# W010X.net
KiCad netlist of a schematic drawn in EAGLE
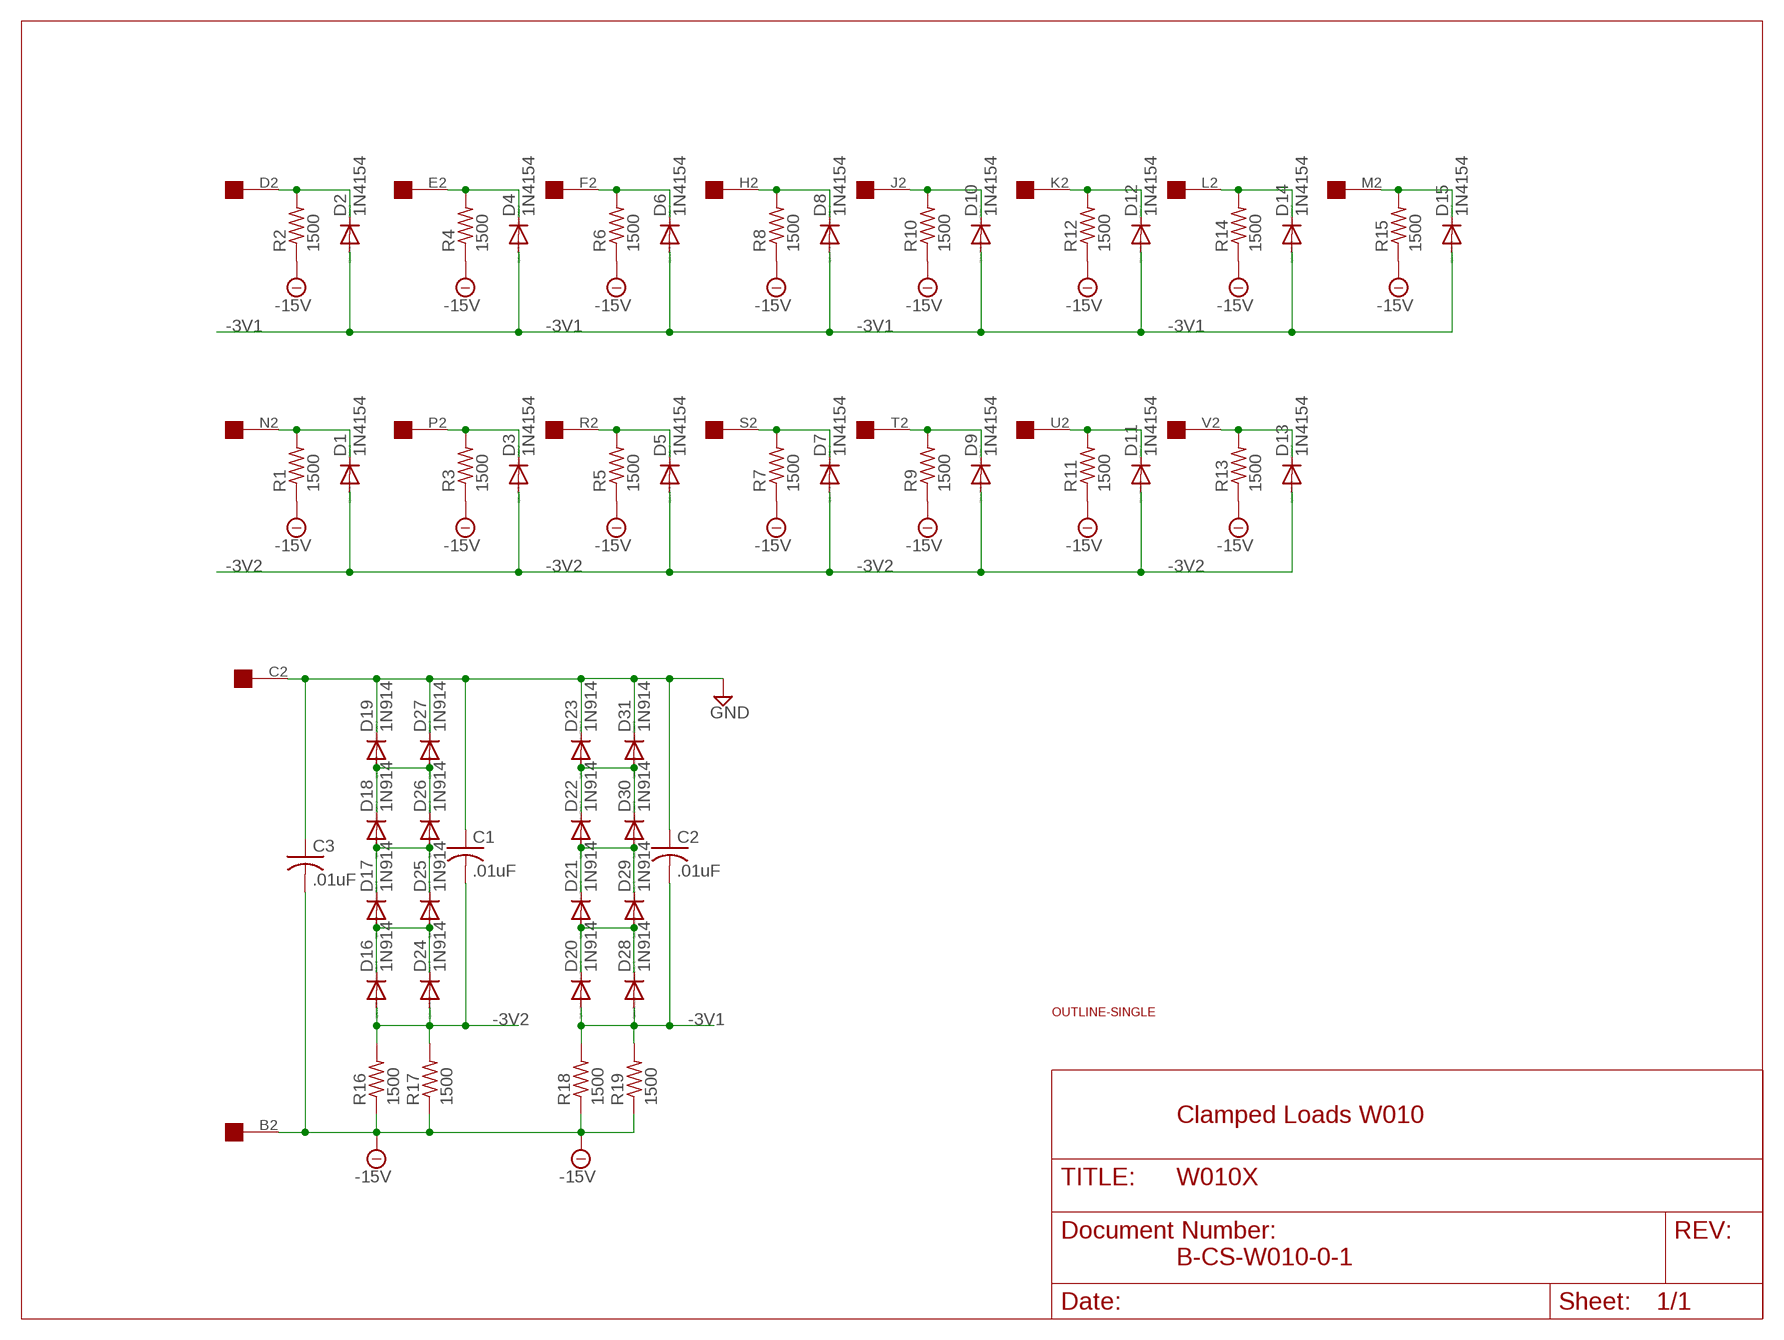
[diagram p0: schematic, sheet 1]

(export (version "E")
  (design (tool "Eeschema 10.0.6"))
  (components
    (comp (ref "C1")
      (value ".01uF")
      (footprint "eagle-import:C063-025X075")
      (libsource (lib "eagle-import") (part "C-US"))
    )
    (comp (ref "C2")
      (value ".01uF")
      (footprint "eagle-import:C063-025X075")
      (libsource (lib "eagle-import") (part "C-US"))
    )
    (comp (ref "C3")
      (value ".01uF")
      (footprint "eagle-import:C063-025X075")
      (libsource (lib "eagle-import") (part "C-US"))
    )
    (comp (ref "D1")
      (value "1N4154")
      (footprint "eagle-import:DO35-10")
      (libsource (lib "eagle-import") (part "DIODE-DO35-10"))
    )
    (comp (ref "D2")
      (value "1N4154")
      (footprint "eagle-import:DO35-10")
      (libsource (lib "eagle-import") (part "DIODE-DO35-10"))
    )
    (comp (ref "D3")
      (value "1N4154")
      (footprint "eagle-import:DO35-10")
      (libsource (lib "eagle-import") (part "DIODE-DO35-10"))
    )
    (comp (ref "D4")
      (value "1N4154")
      (footprint "eagle-import:DO35-10")
      (libsource (lib "eagle-import") (part "DIODE-DO35-10"))
    )
    (comp (ref "D5")
      (value "1N4154")
      (footprint "eagle-import:DO35-10")
      (libsource (lib "eagle-import") (part "DIODE-DO35-10"))
    )
    (comp (ref "D6")
      (value "1N4154")
      (footprint "eagle-import:DO35-10")
      (libsource (lib "eagle-import") (part "DIODE-DO35-10"))
    )
    (comp (ref "D7")
      (value "1N4154")
      (footprint "eagle-import:DO35-10")
      (libsource (lib "eagle-import") (part "DIODE-DO35-10"))
    )
    (comp (ref "D8")
      (value "1N4154")
      (footprint "eagle-import:DO35-10")
      (libsource (lib "eagle-import") (part "DIODE-DO35-10"))
    )
    (comp (ref "D9")
      (value "1N4154")
      (footprint "eagle-import:DO35-10")
      (libsource (lib "eagle-import") (part "DIODE-DO35-10"))
    )
    (comp (ref "D10")
      (value "1N4154")
      (footprint "eagle-import:DO35-10")
      (libsource (lib "eagle-import") (part "DIODE-DO35-10"))
    )
    (comp (ref "D11")
      (value "1N4154")
      (footprint "eagle-import:DO35-10")
      (libsource (lib "eagle-import") (part "DIODE-DO35-10"))
    )
    (comp (ref "D12")
      (value "1N4154")
      (footprint "eagle-import:DO35-10")
      (libsource (lib "eagle-import") (part "DIODE-DO35-10"))
    )
    (comp (ref "D13")
      (value "1N4154")
      (footprint "eagle-import:DO35-10")
      (libsource (lib "eagle-import") (part "DIODE-DO35-10"))
    )
    (comp (ref "D14")
      (value "1N4154")
      (footprint "eagle-import:DO35-10")
      (libsource (lib "eagle-import") (part "DIODE-DO35-10"))
    )
    (comp (ref "D15")
      (value "1N4154")
      (footprint "eagle-import:DO35-10")
      (libsource (lib "eagle-import") (part "DIODE-DO35-10"))
    )
    (comp (ref "D16")
      (value "1N914")
      (footprint "eagle-import:DO35-10")
      (libsource (lib "eagle-import") (part "DIODE-DO35-10"))
    )
    (comp (ref "D17")
      (value "1N914")
      (footprint "eagle-import:DO35-10")
      (libsource (lib "eagle-import") (part "DIODE-DO35-10"))
    )
    (comp (ref "D18")
      (value "1N914")
      (footprint "eagle-import:DO35-10")
      (libsource (lib "eagle-import") (part "DIODE-DO35-10"))
    )
    (comp (ref "D19")
      (value "1N914")
      (footprint "eagle-import:DO35-10")
      (libsource (lib "eagle-import") (part "DIODE-DO35-10"))
    )
    (comp (ref "D20")
      (value "1N914")
      (footprint "eagle-import:DO35-10")
      (libsource (lib "eagle-import") (part "DIODE-DO35-10"))
    )
    (comp (ref "D21")
      (value "1N914")
      (footprint "eagle-import:DO35-10")
      (libsource (lib "eagle-import") (part "DIODE-DO35-10"))
    )
    (comp (ref "D22")
      (value "1N914")
      (footprint "eagle-import:DO35-10")
      (libsource (lib "eagle-import") (part "DIODE-DO35-10"))
    )
    (comp (ref "D23")
      (value "1N914")
      (footprint "eagle-import:DO35-10")
      (libsource (lib "eagle-import") (part "DIODE-DO35-10"))
    )
    (comp (ref "D24")
      (value "1N914")
      (footprint "eagle-import:DO35-10")
      (libsource (lib "eagle-import") (part "DIODE-DO35-10"))
    )
    (comp (ref "D25")
      (value "1N914")
      (footprint "eagle-import:DO35-10")
      (libsource (lib "eagle-import") (part "DIODE-DO35-10"))
    )
    (comp (ref "D26")
      (value "1N914")
      (footprint "eagle-import:DO35-10")
      (libsource (lib "eagle-import") (part "DIODE-DO35-10"))
    )
    (comp (ref "D27")
      (value "1N914")
      (footprint "eagle-import:DO35-10")
      (libsource (lib "eagle-import") (part "DIODE-DO35-10"))
    )
    (comp (ref "D28")
      (value "1N914")
      (footprint "eagle-import:DO35-10")
      (libsource (lib "eagle-import") (part "DIODE-DO35-10"))
    )
    (comp (ref "D29")
      (value "1N914")
      (footprint "eagle-import:DO35-10")
      (libsource (lib "eagle-import") (part "DIODE-DO35-10"))
    )
    (comp (ref "D30")
      (value "1N914")
      (footprint "eagle-import:DO35-10")
      (libsource (lib "eagle-import") (part "DIODE-DO35-10"))
    )
    (comp (ref "D31")
      (value "1N914")
      (footprint "eagle-import:DO35-10")
      (libsource (lib "eagle-import") (part "DIODE-DO35-10"))
    )
    (comp (ref "R1")
      (value "1500")
      (footprint "eagle-import:0207_10")
      (libsource (lib "eagle-import") (part "R-US_0207/10"))
    )
    (comp (ref "R2")
      (value "1500")
      (footprint "eagle-import:0207_10")
      (libsource (lib "eagle-import") (part "R-US_0207/10"))
    )
    (comp (ref "R3")
      (value "1500")
      (footprint "eagle-import:0207_10")
      (libsource (lib "eagle-import") (part "R-US_0207/10"))
    )
    (comp (ref "R4")
      (value "1500")
      (footprint "eagle-import:0207_10")
      (libsource (lib "eagle-import") (part "R-US_0207/10"))
    )
    (comp (ref "R5")
      (value "1500")
      (footprint "eagle-import:0207_10")
      (libsource (lib "eagle-import") (part "R-US_0207/10"))
    )
    (comp (ref "R6")
      (value "1500")
      (footprint "eagle-import:0207_10")
      (libsource (lib "eagle-import") (part "R-US_0207/10"))
    )
    (comp (ref "R7")
      (value "1500")
      (footprint "eagle-import:0207_10")
      (libsource (lib "eagle-import") (part "R-US_0207/10"))
    )
    (comp (ref "R8")
      (value "1500")
      (footprint "eagle-import:0207_10")
      (libsource (lib "eagle-import") (part "R-US_0207/10"))
    )
    (comp (ref "R9")
      (value "1500")
      (footprint "eagle-import:0207_10")
      (libsource (lib "eagle-import") (part "R-US_0207/10"))
    )
    (comp (ref "R10")
      (value "1500")
      (footprint "eagle-import:0207_10")
      (libsource (lib "eagle-import") (part "R-US_0207/10"))
    )
    (comp (ref "R11")
      (value "1500")
      (footprint "eagle-import:0207_10")
      (libsource (lib "eagle-import") (part "R-US_0207/10"))
    )
    (comp (ref "R12")
      (value "1500")
      (footprint "eagle-import:0207_10")
      (libsource (lib "eagle-import") (part "R-US_0207/10"))
    )
    (comp (ref "R13")
      (value "1500")
      (footprint "eagle-import:0207_10")
      (libsource (lib "eagle-import") (part "R-US_0207/10"))
    )
    (comp (ref "R14")
      (value "1500")
      (footprint "eagle-import:0207_10")
      (libsource (lib "eagle-import") (part "R-US_0207/10"))
    )
    (comp (ref "R15")
      (value "1500")
      (footprint "eagle-import:0207_10")
      (libsource (lib "eagle-import") (part "R-US_0207/10"))
    )
    (comp (ref "R16")
      (value "1500")
      (footprint "eagle-import:0207_10")
      (libsource (lib "eagle-import") (part "R-US_0207/10"))
    )
    (comp (ref "R17")
      (value "1500")
      (footprint "eagle-import:0207_10")
      (libsource (lib "eagle-import") (part "R-US_0207/10"))
    )
    (comp (ref "R18")
      (value "1500")
      (footprint "eagle-import:0207_10")
      (libsource (lib "eagle-import") (part "R-US_0207/10"))
    )
    (comp (ref "R19")
      (value "1500")
      (footprint "eagle-import:0207_10")
      (libsource (lib "eagle-import") (part "R-US_0207/10"))
    )
    (comp (ref "U$1")
      (value "EDGE-1")
      (footprint "eagle-import:EDGE-CON1")
      (libsource (lib "eagle-import") (part "EDGE-1"))
    )
    (comp (ref "U$2")
      (value "OUTLINE-SINGLE")
      (footprint "eagle-import:SINGLE")
      (libsource (lib "eagle-import") (part "OUTLINE-SINGLE"))
    )
  )
  (nets
    (net (code "1") (name "-15V") (class "Default")
      (node (ref "C3") (pin "2") (pinfunction "2_2") (pintype "passive"))
      (node (ref "R1") (pin "1") (pinfunction "1_1") (pintype "passive"))
      (node (ref "R10") (pin "1") (pinfunction "1_1") (pintype "passive"))
      (node (ref "R11") (pin "1") (pinfunction "1_1") (pintype "passive"))
      (node (ref "R12") (pin "1") (pinfunction "1_1") (pintype "passive"))
      (node (ref "R13") (pin "1") (pinfunction "1_1") (pintype "passive"))
      (node (ref "R14") (pin "1") (pinfunction "1_1") (pintype "passive"))
      (node (ref "R15") (pin "1") (pinfunction "1_1") (pintype "passive"))
      (node (ref "R16") (pin "1") (pinfunction "1_1") (pintype "passive"))
      (node (ref "R17") (pin "1") (pinfunction "1_1") (pintype "passive"))
      (node (ref "R18") (pin "1") (pinfunction "1_1") (pintype "passive"))
      (node (ref "R19") (pin "1") (pinfunction "1_1") (pintype "passive"))
      (node (ref "R2") (pin "1") (pinfunction "1_1") (pintype "passive"))
      (node (ref "R3") (pin "1") (pinfunction "1_1") (pintype "passive"))
      (node (ref "R4") (pin "1") (pinfunction "1_1") (pintype "passive"))
      (node (ref "R5") (pin "1") (pinfunction "1_1") (pintype "passive"))
      (node (ref "R6") (pin "1") (pinfunction "1_1") (pintype "passive"))
      (node (ref "R7") (pin "1") (pinfunction "1_1") (pintype "passive"))
      (node (ref "R8") (pin "1") (pinfunction "1_1") (pintype "passive"))
      (node (ref "R9") (pin "1") (pinfunction "1_1") (pintype "passive"))
      (node (ref "U$1") (pin "B2") (pinfunction "1_B2") (pintype "bidirectional"))
    )
    (net (code "2") (name "/-3V1") (class "Default")
      (node (ref "C2") (pin "2") (pinfunction "2_2") (pintype "passive"))
      (node (ref "D10") (pin "A") (pinfunction "A_A") (pintype "passive"))
      (node (ref "D12") (pin "A") (pinfunction "A_A") (pintype "passive"))
      (node (ref "D14") (pin "A") (pinfunction "A_A") (pintype "passive"))
      (node (ref "D15") (pin "A") (pinfunction "A_A") (pintype "passive"))
      (node (ref "D2") (pin "A") (pinfunction "A_A") (pintype "passive"))
      (node (ref "D20") (pin "A") (pinfunction "A_A") (pintype "passive"))
      (node (ref "D28") (pin "A") (pinfunction "A_A") (pintype "passive"))
      (node (ref "D4") (pin "A") (pinfunction "A_A") (pintype "passive"))
      (node (ref "D6") (pin "A") (pinfunction "A_A") (pintype "passive"))
      (node (ref "D8") (pin "A") (pinfunction "A_A") (pintype "passive"))
      (node (ref "R18") (pin "2") (pinfunction "2_2") (pintype "passive"))
      (node (ref "R19") (pin "2") (pinfunction "2_2") (pintype "passive"))
    )
    (net (code "3") (name "/-3V2") (class "Default")
      (node (ref "C1") (pin "2") (pinfunction "2_2") (pintype "passive"))
      (node (ref "D1") (pin "A") (pinfunction "A_A") (pintype "passive"))
      (node (ref "D11") (pin "A") (pinfunction "A_A") (pintype "passive"))
      (node (ref "D13") (pin "A") (pinfunction "A_A") (pintype "passive"))
      (node (ref "D16") (pin "A") (pinfunction "A_A") (pintype "passive"))
      (node (ref "D24") (pin "A") (pinfunction "A_A") (pintype "passive"))
      (node (ref "D3") (pin "A") (pinfunction "A_A") (pintype "passive"))
      (node (ref "D5") (pin "A") (pinfunction "A_A") (pintype "passive"))
      (node (ref "D7") (pin "A") (pinfunction "A_A") (pintype "passive"))
      (node (ref "D9") (pin "A") (pinfunction "A_A") (pintype "passive"))
      (node (ref "R16") (pin "2") (pinfunction "2_2") (pintype "passive"))
      (node (ref "R17") (pin "2") (pinfunction "2_2") (pintype "passive"))
    )
    (net (code "4") (name "GND") (class "Default")
      (node (ref "C1") (pin "1") (pinfunction "1_1") (pintype "passive"))
      (node (ref "C2") (pin "1") (pinfunction "1_1") (pintype "passive"))
      (node (ref "C3") (pin "1") (pinfunction "1_1") (pintype "passive"))
      (node (ref "D19") (pin "C") (pinfunction "C_C") (pintype "passive"))
      (node (ref "D23") (pin "C") (pinfunction "C_C") (pintype "passive"))
      (node (ref "D27") (pin "C") (pinfunction "C_C") (pintype "passive"))
      (node (ref "D31") (pin "C") (pinfunction "C_C") (pintype "passive"))
      (node (ref "U$1") (pin "C2") (pinfunction "1_C2") (pintype "bidirectional"))
    )
    (net (code "5") (name "Net-(D16-PadC)") (class "Default")
      (node (ref "D16") (pin "C") (pinfunction "C_C") (pintype "passive"))
      (node (ref "D17") (pin "A") (pinfunction "A_A") (pintype "passive"))
      (node (ref "D24") (pin "C") (pinfunction "C_C") (pintype "passive"))
      (node (ref "D25") (pin "A") (pinfunction "A_A") (pintype "passive"))
    )
    (net (code "6") (name "Net-(D17-PadC)") (class "Default")
      (node (ref "D17") (pin "C") (pinfunction "C_C") (pintype "passive"))
      (node (ref "D18") (pin "A") (pinfunction "A_A") (pintype "passive"))
      (node (ref "D25") (pin "C") (pinfunction "C_C") (pintype "passive"))
      (node (ref "D26") (pin "A") (pinfunction "A_A") (pintype "passive"))
    )
    (net (code "7") (name "Net-(D18-PadC)") (class "Default")
      (node (ref "D18") (pin "C") (pinfunction "C_C") (pintype "passive"))
      (node (ref "D19") (pin "A") (pinfunction "A_A") (pintype "passive"))
      (node (ref "D26") (pin "C") (pinfunction "C_C") (pintype "passive"))
      (node (ref "D27") (pin "A") (pinfunction "A_A") (pintype "passive"))
    )
    (net (code "8") (name "Net-(D20-PadC)") (class "Default")
      (node (ref "D20") (pin "C") (pinfunction "C_C") (pintype "passive"))
      (node (ref "D21") (pin "A") (pinfunction "A_A") (pintype "passive"))
      (node (ref "D28") (pin "C") (pinfunction "C_C") (pintype "passive"))
      (node (ref "D29") (pin "A") (pinfunction "A_A") (pintype "passive"))
    )
    (net (code "9") (name "Net-(D21-PadC)") (class "Default")
      (node (ref "D21") (pin "C") (pinfunction "C_C") (pintype "passive"))
      (node (ref "D22") (pin "A") (pinfunction "A_A") (pintype "passive"))
      (node (ref "D29") (pin "C") (pinfunction "C_C") (pintype "passive"))
      (node (ref "D30") (pin "A") (pinfunction "A_A") (pintype "passive"))
    )
    (net (code "10") (name "Net-(D22-PadC)") (class "Default")
      (node (ref "D22") (pin "C") (pinfunction "C_C") (pintype "passive"))
      (node (ref "D23") (pin "A") (pinfunction "A_A") (pintype "passive"))
      (node (ref "D30") (pin "C") (pinfunction "C_C") (pintype "passive"))
      (node (ref "D31") (pin "A") (pinfunction "A_A") (pintype "passive"))
    )
    (net (code "11") (name "Net-(U$1D-1)") (class "Default")
      (node (ref "D2") (pin "C") (pinfunction "C_C") (pintype "passive"))
      (node (ref "R2") (pin "2") (pinfunction "2_2") (pintype "passive"))
      (node (ref "U$1") (pin "D2") (pinfunction "1_D2") (pintype "bidirectional"))
    )
    (net (code "12") (name "Net-(U$1E-1)") (class "Default")
      (node (ref "D4") (pin "C") (pinfunction "C_C") (pintype "passive"))
      (node (ref "R4") (pin "2") (pinfunction "2_2") (pintype "passive"))
      (node (ref "U$1") (pin "E2") (pinfunction "1_E2") (pintype "bidirectional"))
    )
    (net (code "13") (name "Net-(U$1F-1)") (class "Default")
      (node (ref "D6") (pin "C") (pinfunction "C_C") (pintype "passive"))
      (node (ref "R6") (pin "2") (pinfunction "2_2") (pintype "passive"))
      (node (ref "U$1") (pin "F2") (pinfunction "1_F2") (pintype "bidirectional"))
    )
    (net (code "14") (name "Net-(U$1G-1)") (class "Default")
      (node (ref "D8") (pin "C") (pinfunction "C_C") (pintype "passive"))
      (node (ref "R8") (pin "2") (pinfunction "2_2") (pintype "passive"))
      (node (ref "U$1") (pin "H2") (pinfunction "1_H2") (pintype "bidirectional"))
    )
    (net (code "15") (name "Net-(U$1H-1)") (class "Default")
      (node (ref "D10") (pin "C") (pinfunction "C_C") (pintype "passive"))
      (node (ref "R10") (pin "2") (pinfunction "2_2") (pintype "passive"))
      (node (ref "U$1") (pin "J2") (pinfunction "1_J2") (pintype "bidirectional"))
    )
    (net (code "16") (name "Net-(U$1I-1)") (class "Default")
      (node (ref "D12") (pin "C") (pinfunction "C_C") (pintype "passive"))
      (node (ref "R12") (pin "2") (pinfunction "2_2") (pintype "passive"))
      (node (ref "U$1") (pin "K2") (pinfunction "1_K2") (pintype "bidirectional"))
    )
    (net (code "17") (name "Net-(U$1J-1)") (class "Default")
      (node (ref "D14") (pin "C") (pinfunction "C_C") (pintype "passive"))
      (node (ref "R14") (pin "2") (pinfunction "2_2") (pintype "passive"))
      (node (ref "U$1") (pin "L2") (pinfunction "1_L2") (pintype "bidirectional"))
    )
    (net (code "18") (name "Net-(U$1K-1)") (class "Default")
      (node (ref "D15") (pin "C") (pinfunction "C_C") (pintype "passive"))
      (node (ref "R15") (pin "2") (pinfunction "2_2") (pintype "passive"))
      (node (ref "U$1") (pin "M2") (pinfunction "1_M2") (pintype "bidirectional"))
    )
    (net (code "19") (name "Net-(U$1L-1)") (class "Default")
      (node (ref "D1") (pin "C") (pinfunction "C_C") (pintype "passive"))
      (node (ref "R1") (pin "2") (pinfunction "2_2") (pintype "passive"))
      (node (ref "U$1") (pin "N2") (pinfunction "1_N2") (pintype "bidirectional"))
    )
    (net (code "20") (name "Net-(U$1M-1)") (class "Default")
      (node (ref "D3") (pin "C") (pinfunction "C_C") (pintype "passive"))
      (node (ref "R3") (pin "2") (pinfunction "2_2") (pintype "passive"))
      (node (ref "U$1") (pin "P2") (pinfunction "1_P2") (pintype "bidirectional"))
    )
    (net (code "21") (name "Net-(U$1N-1)") (class "Default")
      (node (ref "D5") (pin "C") (pinfunction "C_C") (pintype "passive"))
      (node (ref "R5") (pin "2") (pinfunction "2_2") (pintype "passive"))
      (node (ref "U$1") (pin "R2") (pinfunction "1_R2") (pintype "bidirectional"))
    )
    (net (code "22") (name "Net-(U$1O-1)") (class "Default")
      (node (ref "D7") (pin "C") (pinfunction "C_C") (pintype "passive"))
      (node (ref "R7") (pin "2") (pinfunction "2_2") (pintype "passive"))
      (node (ref "U$1") (pin "S2") (pinfunction "1_S2") (pintype "bidirectional"))
    )
    (net (code "23") (name "Net-(U$1P-1)") (class "Default")
      (node (ref "D9") (pin "C") (pinfunction "C_C") (pintype "passive"))
      (node (ref "R9") (pin "2") (pinfunction "2_2") (pintype "passive"))
      (node (ref "U$1") (pin "T2") (pinfunction "1_T2") (pintype "bidirectional"))
    )
    (net (code "24") (name "Net-(U$1Q-1)") (class "Default")
      (node (ref "D11") (pin "C") (pinfunction "C_C") (pintype "passive"))
      (node (ref "R11") (pin "2") (pinfunction "2_2") (pintype "passive"))
      (node (ref "U$1") (pin "U2") (pinfunction "1_U2") (pintype "bidirectional"))
    )
    (net (code "25") (name "Net-(U$1R-1)") (class "Default")
      (node (ref "D13") (pin "C") (pinfunction "C_C") (pintype "passive"))
      (node (ref "R13") (pin "2") (pinfunction "2_2") (pintype "passive"))
      (node (ref "U$1") (pin "V2") (pinfunction "1_V2") (pintype "bidirectional"))
    )
  )
)
